# Buttons.net
KiCad netlist of a schematic drawn in Altium Designer
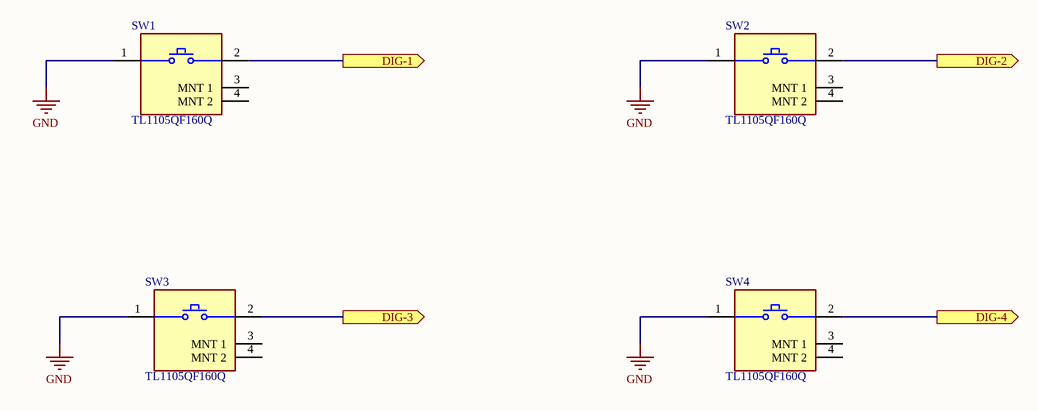
[diagram p0: Buttons.SchDoc]

(export (version "E")
  (design (tool "Eeschema 10.0.6"))
  (components
    (comp (ref "SW1")
      (value "TL1105QF160Q")
      (footprint "FP-TL1105QF160Q-MFG")
      (description "Tactile Switches 6mm R/A 5/8\" ACTUATR")
      (fields (field (name "MANUFACTURER") "E-Switch"))
      (libsource (lib "Altium Content Vault") (part "61b760406b2cfde6e730dd07927510b"))
    )
    (comp (ref "SW2")
      (value "TL1105QF160Q")
      (footprint "FP-TL1105QF160Q-MFG")
      (description "Tactile Switches 6mm R/A 5/8\" ACTUATR")
      (fields (field (name "MANUFACTURER") "E-Switch"))
      (libsource (lib "Altium Content Vault") (part "61b760406b2cfde6e730dd07927510b"))
    )
    (comp (ref "SW3")
      (value "TL1105QF160Q")
      (footprint "FP-TL1105QF160Q-MFG")
      (description "Tactile Switches 6mm R/A 5/8\" ACTUATR")
      (fields (field (name "MANUFACTURER") "E-Switch"))
      (libsource (lib "Altium Content Vault") (part "61b760406b2cfde6e730dd07927510b"))
    )
    (comp (ref "SW4")
      (value "TL1105QF160Q")
      (footprint "FP-TL1105QF160Q-MFG")
      (description "Tactile Switches 6mm R/A 5/8\" ACTUATR")
      (fields (field (name "MANUFACTURER") "E-Switch"))
      (libsource (lib "Altium Content Vault") (part "61b760406b2cfde6e730dd07927510b"))
    )
  )
  (nets
    (net (code "1") (name "/DIG-1") (class "Default")
      (node (ref "SW1") (pin "2") (pinfunction "2_2") (pintype "passive"))
    )
    (net (code "2") (name "/DIG-2") (class "Default")
      (node (ref "SW2") (pin "2") (pinfunction "2_2") (pintype "passive"))
    )
    (net (code "3") (name "/DIG-3") (class "Default")
      (node (ref "SW3") (pin "2") (pinfunction "2_2") (pintype "passive"))
    )
    (net (code "4") (name "/DIG-4") (class "Default")
      (node (ref "SW4") (pin "2") (pinfunction "2_2") (pintype "passive"))
    )
    (net (code "5") (name "GND") (class "Default")
      (node (ref "SW1") (pin "1") (pinfunction "1_1") (pintype "passive"))
      (node (ref "SW2") (pin "1") (pinfunction "1_1") (pintype "passive"))
      (node (ref "SW3") (pin "1") (pinfunction "1_1") (pintype "passive"))
      (node (ref "SW4") (pin "1") (pinfunction "1_1") (pintype "passive"))
    )
    (net (code "6") (name "unconnected-(SW1-MNT_1-Pad3)") (class "Default")
      (node (ref "SW1") (pin "3") (pinfunction "MNT_1_3") (pintype "passive"))
    )
    (net (code "7") (name "unconnected-(SW1-MNT_2-Pad4)") (class "Default")
      (node (ref "SW1") (pin "4") (pinfunction "MNT_2_4") (pintype "passive"))
    )
    (net (code "8") (name "unconnected-(SW2-MNT_1-Pad3)") (class "Default")
      (node (ref "SW2") (pin "3") (pinfunction "MNT_1_3") (pintype "passive"))
    )
    (net (code "9") (name "unconnected-(SW2-MNT_2-Pad4)") (class "Default")
      (node (ref "SW2") (pin "4") (pinfunction "MNT_2_4") (pintype "passive"))
    )
    (net (code "10") (name "unconnected-(SW3-MNT_1-Pad3)") (class "Default")
      (node (ref "SW3") (pin "3") (pinfunction "MNT_1_3") (pintype "passive"))
    )
    (net (code "11") (name "unconnected-(SW3-MNT_2-Pad4)") (class "Default")
      (node (ref "SW3") (pin "4") (pinfunction "MNT_2_4") (pintype "passive"))
    )
    (net (code "12") (name "unconnected-(SW4-MNT_1-Pad3)") (class "Default")
      (node (ref "SW4") (pin "3") (pinfunction "MNT_1_3") (pintype "passive"))
    )
    (net (code "13") (name "unconnected-(SW4-MNT_2-Pad4)") (class "Default")
      (node (ref "SW4") (pin "4") (pinfunction "MNT_2_4") (pintype "passive"))
    )
  )
)
